# EnigmaMon.net
KiCad netlist of a schematic drawn in EAGLE
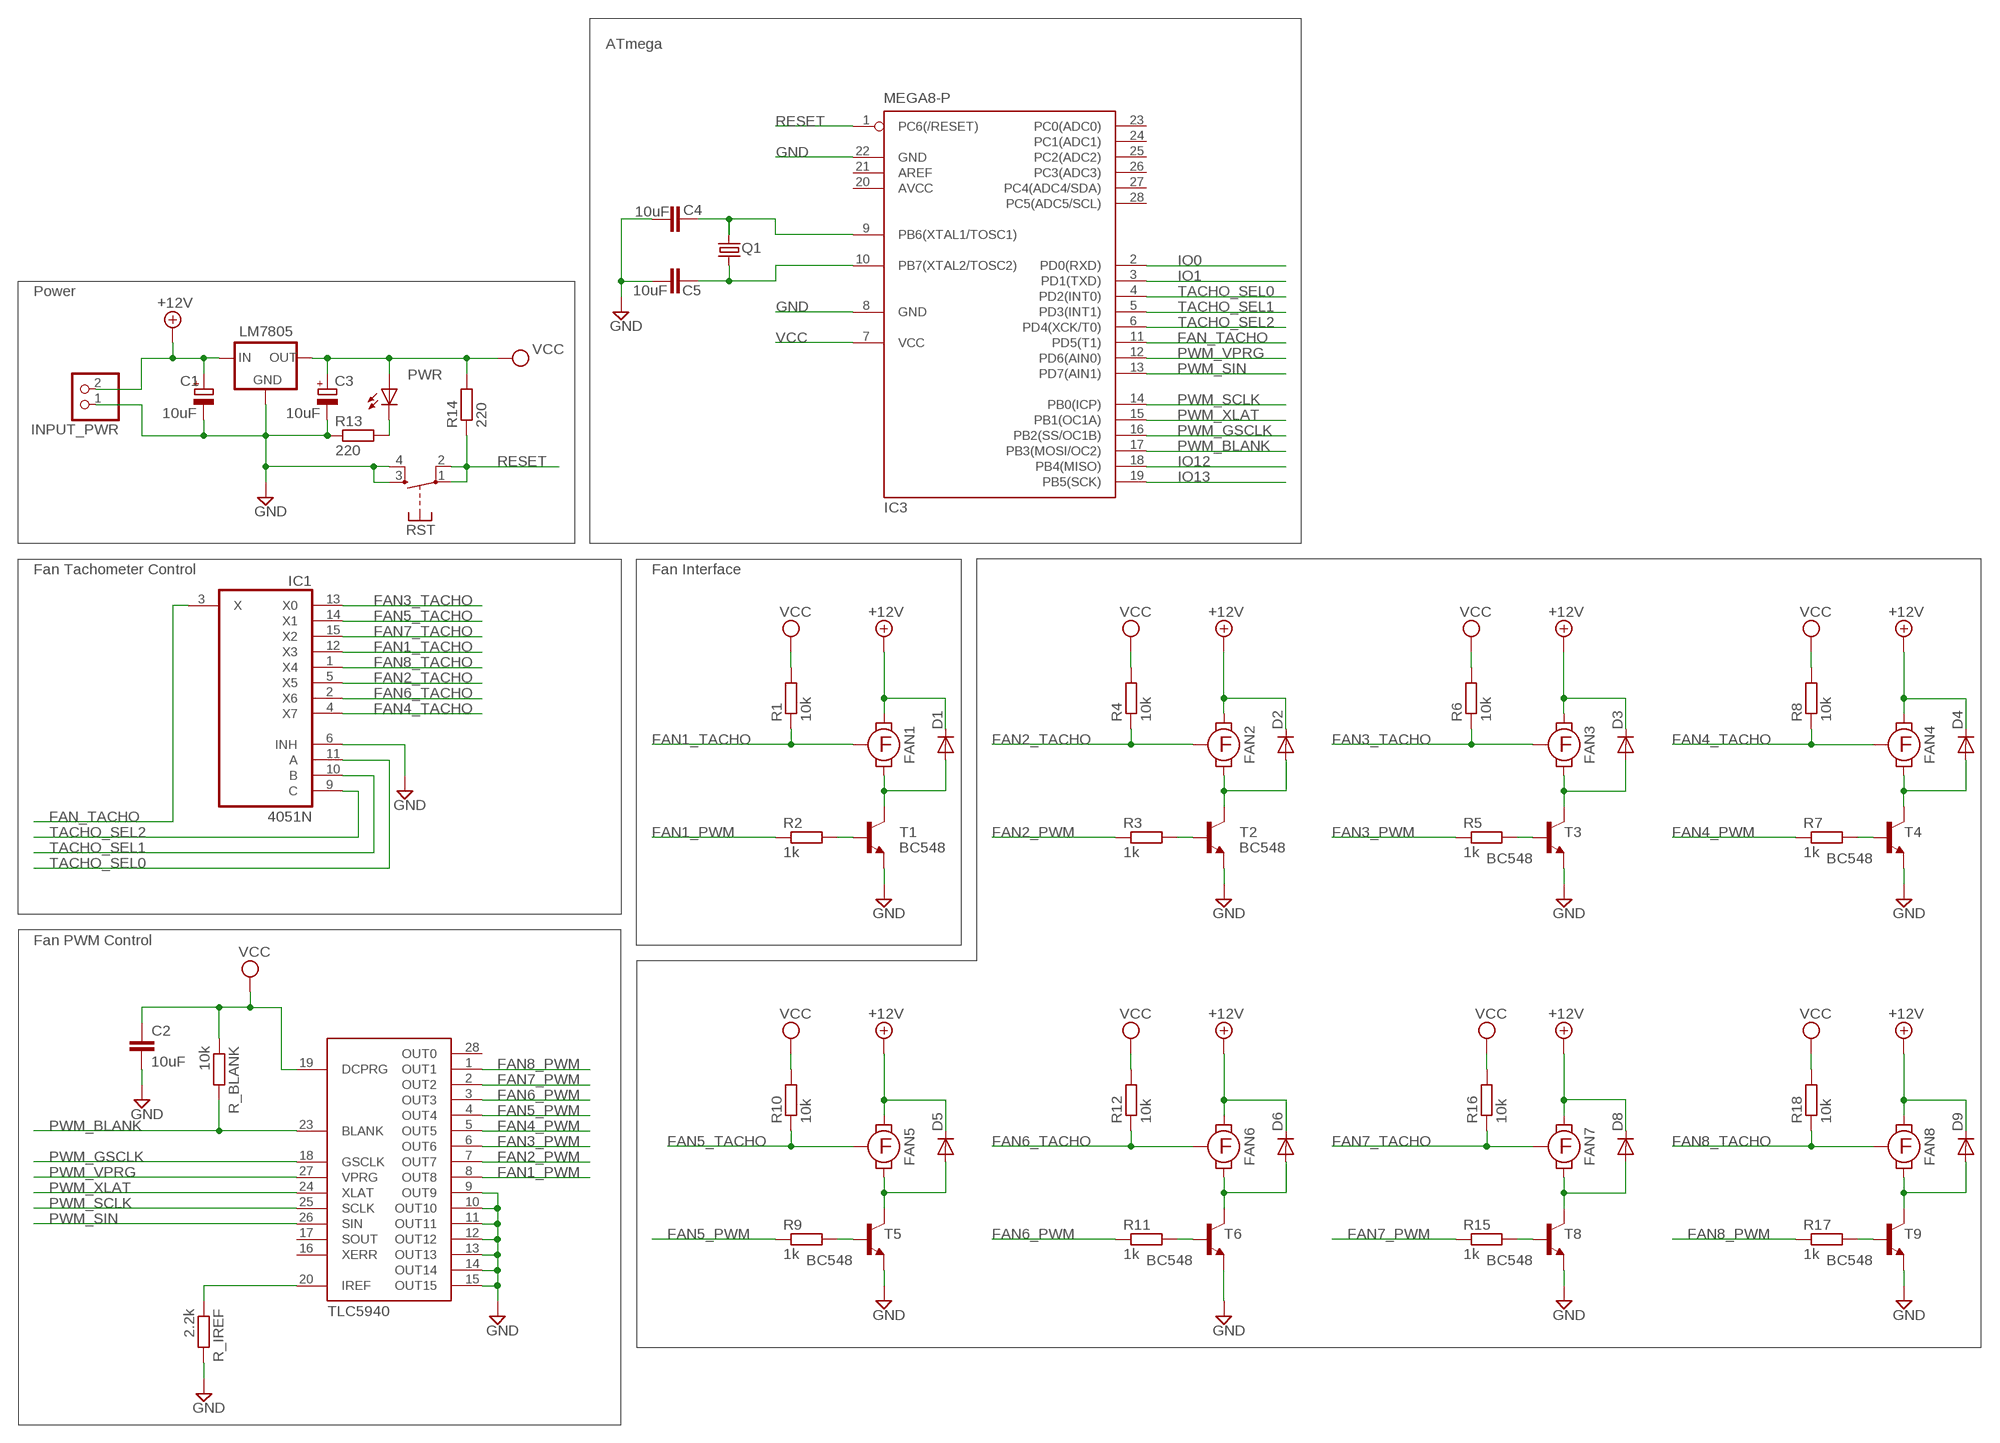
[diagram p0: schematic, sheet 1]

(export (version "E")
  (design (tool "Eeschema 10.0.6"))
  (components
    (comp (ref "C1")
      (value "10uF")
      (footprint "eagle-import:E2,5-6")
      (libsource (lib "eagle-import") (part "CPOL-EUE2.5-6"))
    )
    (comp (ref "C2")
      (value "10uF")
      (footprint "eagle-import:C025-025X050")
      (libsource (lib "eagle-import") (part "C-EU025-025X050"))
    )
    (comp (ref "C3")
      (value "10uF")
      (footprint "eagle-import:E2,5-6")
      (libsource (lib "eagle-import") (part "CPOL-EUE2.5-6"))
    )
    (comp (ref "C4")
      (value "10uF")
      (footprint "eagle-import:C025-025X050")
      (libsource (lib "eagle-import") (part "C-EU025-025X050"))
    )
    (comp (ref "C5")
      (value "10uF")
      (footprint "eagle-import:C025-025X050")
      (libsource (lib "eagle-import") (part "C-EU025-025X050"))
    )
    (comp (ref "D1")
      (value "DIODE-D-5")
      (footprint "eagle-import:D-5")
      (libsource (lib "eagle-import") (part "DIODE-D-5"))
    )
    (comp (ref "D2")
      (value "DIODE-D-5")
      (footprint "eagle-import:D-5")
      (libsource (lib "eagle-import") (part "DIODE-D-5"))
    )
    (comp (ref "D3")
      (value "DIODE-D-5")
      (footprint "eagle-import:D-5")
      (libsource (lib "eagle-import") (part "DIODE-D-5"))
    )
    (comp (ref "D4")
      (value "DIODE-D-5")
      (footprint "eagle-import:D-5")
      (libsource (lib "eagle-import") (part "DIODE-D-5"))
    )
    (comp (ref "D5")
      (value "DIODE-D-5")
      (footprint "eagle-import:D-5")
      (libsource (lib "eagle-import") (part "DIODE-D-5"))
    )
    (comp (ref "D6")
      (value "DIODE-D-5")
      (footprint "eagle-import:D-5")
      (libsource (lib "eagle-import") (part "DIODE-D-5"))
    )
    (comp (ref "D8")
      (value "DIODE-D-5")
      (footprint "eagle-import:D-5")
      (libsource (lib "eagle-import") (part "DIODE-D-5"))
    )
    (comp (ref "D9")
      (value "DIODE-D-5")
      (footprint "eagle-import:D-5")
      (libsource (lib "eagle-import") (part "DIODE-D-5"))
    )
    (comp (ref "FAN1")
      (value "FAN")
      (footprint "eagle-import:FAN_HEADER")
      (libsource (lib "eagle-import") (part "FAN"))
    )
    (comp (ref "FAN2")
      (value "FAN")
      (footprint "eagle-import:FAN_HEADER")
      (libsource (lib "eagle-import") (part "FAN"))
    )
    (comp (ref "FAN3")
      (value "FAN")
      (footprint "eagle-import:FAN_HEADER")
      (libsource (lib "eagle-import") (part "FAN"))
    )
    (comp (ref "FAN4")
      (value "FAN")
      (footprint "eagle-import:FAN_HEADER")
      (libsource (lib "eagle-import") (part "FAN"))
    )
    (comp (ref "FAN5")
      (value "FAN")
      (footprint "eagle-import:FAN_HEADER")
      (libsource (lib "eagle-import") (part "FAN"))
    )
    (comp (ref "FAN6")
      (value "FAN")
      (footprint "eagle-import:FAN_HEADER")
      (libsource (lib "eagle-import") (part "FAN"))
    )
    (comp (ref "FAN7")
      (value "FAN")
      (footprint "eagle-import:FAN_HEADER")
      (libsource (lib "eagle-import") (part "FAN"))
    )
    (comp (ref "FAN8")
      (value "FAN")
      (footprint "eagle-import:FAN_HEADER")
      (libsource (lib "eagle-import") (part "FAN"))
    )
    (comp (ref "IC1")
      (value "4051N")
      (footprint "eagle-import:DIL16")
      (libsource (lib "eagle-import") (part "4051N"))
    )
    (comp (ref "IC2")
      (value "TLC5940")
      (footprint "eagle-import:DIL28-3")
      (libsource (lib "eagle-import") (part "TLC5940"))
    )
    (comp (ref "IC3")
      (value "MEGA8-P")
      (footprint "eagle-import:DIL28-3")
      (libsource (lib "eagle-import") (part "MEGA8-P"))
    )
    (comp (ref "INPUT_PWR")
      (value "PINHD-1X2")
      (footprint "eagle-import:1X02")
      (libsource (lib "eagle-import") (part "PINHD-1X2"))
    )
    (comp (ref "LM7805")
      (value "78XXL")
      (footprint "eagle-import:78XXL")
      (libsource (lib "eagle-import") (part "78XXL"))
    )
    (comp (ref "PWR")
      (value "LED3MM")
      (footprint "eagle-import:LED3MM")
      (libsource (lib "eagle-import") (part "LED3MM"))
    )
    (comp (ref "Q1")
      (value "CRYSTALHC49S")
      (footprint "eagle-import:HC49_S")
      (libsource (lib "eagle-import") (part "CRYSTALHC49S"))
    )
    (comp (ref "R1")
      (value "10k")
      (footprint "eagle-import:0204_5")
      (libsource (lib "eagle-import") (part "R-EU_0204/5"))
    )
    (comp (ref "R2")
      (value "1k")
      (footprint "eagle-import:0204_5")
      (libsource (lib "eagle-import") (part "R-EU_0204/5"))
    )
    (comp (ref "R3")
      (value "1k")
      (footprint "eagle-import:0204_5")
      (libsource (lib "eagle-import") (part "R-EU_0204/5"))
    )
    (comp (ref "R4")
      (value "10k")
      (footprint "eagle-import:0204_5")
      (libsource (lib "eagle-import") (part "R-EU_0204/5"))
    )
    (comp (ref "R5")
      (value "1k")
      (footprint "eagle-import:0204_5")
      (libsource (lib "eagle-import") (part "R-EU_0204/5"))
    )
    (comp (ref "R6")
      (value "10k")
      (footprint "eagle-import:0204_5")
      (libsource (lib "eagle-import") (part "R-EU_0204/5"))
    )
    (comp (ref "R7")
      (value "1k")
      (footprint "eagle-import:0204_5")
      (libsource (lib "eagle-import") (part "R-EU_0204/5"))
    )
    (comp (ref "R8")
      (value "10k")
      (footprint "eagle-import:0204_5")
      (libsource (lib "eagle-import") (part "R-EU_0204/5"))
    )
    (comp (ref "R9")
      (value "1k")
      (footprint "eagle-import:0204_5")
      (libsource (lib "eagle-import") (part "R-EU_0204/5"))
    )
    (comp (ref "R10")
      (value "10k")
      (footprint "eagle-import:0204_5")
      (libsource (lib "eagle-import") (part "R-EU_0204/5"))
    )
    (comp (ref "R11")
      (value "1k")
      (footprint "eagle-import:0204_5")
      (libsource (lib "eagle-import") (part "R-EU_0204/5"))
    )
    (comp (ref "R12")
      (value "10k")
      (footprint "eagle-import:0204_5")
      (libsource (lib "eagle-import") (part "R-EU_0204/5"))
    )
    (comp (ref "R13")
      (value "220")
      (footprint "eagle-import:0204_7")
      (libsource (lib "eagle-import") (part "R-EU_0204/7"))
    )
    (comp (ref "R14")
      (value "220")
      (footprint "eagle-import:0204_7")
      (libsource (lib "eagle-import") (part "R-EU_0204/7"))
    )
    (comp (ref "R15")
      (value "1k")
      (footprint "eagle-import:0204_5")
      (libsource (lib "eagle-import") (part "R-EU_0204/5"))
    )
    (comp (ref "R16")
      (value "10k")
      (footprint "eagle-import:0204_5")
      (libsource (lib "eagle-import") (part "R-EU_0204/5"))
    )
    (comp (ref "R17")
      (value "1k")
      (footprint "eagle-import:0204_5")
      (libsource (lib "eagle-import") (part "R-EU_0204/5"))
    )
    (comp (ref "R18")
      (value "10k")
      (footprint "eagle-import:0204_5")
      (libsource (lib "eagle-import") (part "R-EU_0204/5"))
    )
    (comp (ref "RST")
      (value "DTS6")
      (footprint "eagle-import:DTS6")
      (libsource (lib "eagle-import") (part "DTS6"))
    )
    (comp (ref "R_BLANK")
      (value "10k")
      (footprint "eagle-import:0204_7")
      (libsource (lib "eagle-import") (part "R-EU_0204/7"))
    )
    (comp (ref "R_IREF")
      (value "2.2k")
      (footprint "eagle-import:0204_7")
      (libsource (lib "eagle-import") (part "R-EU_0204/7"))
    )
    (comp (ref "T1")
      (value "BC548")
      (footprint "eagle-import:TO92")
      (libsource (lib "eagle-import") (part "BC547"))
    )
    (comp (ref "T2")
      (value "BC548")
      (footprint "eagle-import:TO92")
      (libsource (lib "eagle-import") (part "BC547"))
    )
    (comp (ref "T3")
      (value "BC548")
      (footprint "eagle-import:TO92")
      (libsource (lib "eagle-import") (part "BC547"))
    )
    (comp (ref "T4")
      (value "BC548")
      (footprint "eagle-import:TO92")
      (libsource (lib "eagle-import") (part "BC547"))
    )
    (comp (ref "T5")
      (value "BC548")
      (footprint "eagle-import:TO92")
      (libsource (lib "eagle-import") (part "BC547"))
    )
    (comp (ref "T6")
      (value "BC548")
      (footprint "eagle-import:TO92")
      (libsource (lib "eagle-import") (part "BC547"))
    )
    (comp (ref "T8")
      (value "BC548")
      (footprint "eagle-import:TO92")
      (libsource (lib "eagle-import") (part "BC547"))
    )
    (comp (ref "T9")
      (value "BC548")
      (footprint "eagle-import:TO92")
      (libsource (lib "eagle-import") (part "BC547"))
    )
  )
  (nets
    (net (code "1") (name "+12V") (class "Default")
      (node (ref "C1") (pin "+") (pinfunction "+_+") (pintype "passive"))
      (node (ref "D1") (pin "C") (pinfunction "C_C") (pintype "passive"))
      (node (ref "D2") (pin "C") (pinfunction "C_C") (pintype "passive"))
      (node (ref "D3") (pin "C") (pinfunction "C_C") (pintype "passive"))
      (node (ref "D4") (pin "C") (pinfunction "C_C") (pintype "passive"))
      (node (ref "D5") (pin "C") (pinfunction "C_C") (pintype "passive"))
      (node (ref "D6") (pin "C") (pinfunction "C_C") (pintype "passive"))
      (node (ref "D8") (pin "C") (pinfunction "C_C") (pintype "passive"))
      (node (ref "D9") (pin "C") (pinfunction "C_C") (pintype "passive"))
      (node (ref "FAN1") (pin "VCC") (pinfunction "VCC_VCC") (pintype "power_in"))
      (node (ref "FAN2") (pin "VCC") (pinfunction "VCC_VCC") (pintype "power_in"))
      (node (ref "FAN3") (pin "VCC") (pinfunction "VCC_VCC") (pintype "power_in"))
      (node (ref "FAN4") (pin "VCC") (pinfunction "VCC_VCC") (pintype "power_in"))
      (node (ref "FAN5") (pin "VCC") (pinfunction "VCC_VCC") (pintype "power_in"))
      (node (ref "FAN6") (pin "VCC") (pinfunction "VCC_VCC") (pintype "power_in"))
      (node (ref "FAN7") (pin "VCC") (pinfunction "VCC_VCC") (pintype "power_in"))
      (node (ref "FAN8") (pin "VCC") (pinfunction "VCC_VCC") (pintype "power_in"))
      (node (ref "INPUT_PWR") (pin "2") (pinfunction "2_2") (pintype "passive"))
      (node (ref "LM7805") (pin "IN") (pinfunction "IN_IN") (pintype "input"))
    )
    (net (code "2") (name "/AVCC") (class "Default")
      (node (ref "IC3") (pin "20") (pinfunction "AVCC_20") (pintype "power_in"))
    )
    (net (code "3") (name "/FAN1_PWM") (class "Default")
      (node (ref "IC2") (pin "8") (pinfunction "OUT8_8") (pintype "output"))
      (node (ref "R2") (pin "1") (pinfunction "1_1") (pintype "passive"))
    )
    (net (code "4") (name "/FAN1_TACHO") (class "Default")
      (node (ref "FAN1") (pin "TACHO") (pinfunction "TACHO_TACHO") (pintype "output"))
      (node (ref "IC1") (pin "12") (pinfunction "X3_12") (pintype "bidirectional"))
      (node (ref "R1") (pin "1") (pinfunction "1_1") (pintype "passive"))
    )
    (net (code "5") (name "/FAN2_PWM") (class "Default")
      (node (ref "IC2") (pin "7") (pinfunction "OUT7_7") (pintype "output"))
      (node (ref "R3") (pin "1") (pinfunction "1_1") (pintype "passive"))
    )
    (net (code "6") (name "/FAN2_TACHO") (class "Default")
      (node (ref "FAN2") (pin "TACHO") (pinfunction "TACHO_TACHO") (pintype "output"))
      (node (ref "IC1") (pin "5") (pinfunction "X5_5") (pintype "bidirectional"))
      (node (ref "R4") (pin "1") (pinfunction "1_1") (pintype "passive"))
    )
    (net (code "7") (name "/FAN3_PWM") (class "Default")
      (node (ref "IC2") (pin "6") (pinfunction "OUT6_6") (pintype "output"))
      (node (ref "R5") (pin "1") (pinfunction "1_1") (pintype "passive"))
    )
    (net (code "8") (name "/FAN3_TACHO") (class "Default")
      (node (ref "FAN3") (pin "TACHO") (pinfunction "TACHO_TACHO") (pintype "output"))
      (node (ref "IC1") (pin "13") (pinfunction "X0_13") (pintype "bidirectional"))
      (node (ref "R6") (pin "1") (pinfunction "1_1") (pintype "passive"))
    )
    (net (code "9") (name "/FAN4_PWM") (class "Default")
      (node (ref "IC2") (pin "5") (pinfunction "OUT5_5") (pintype "output"))
      (node (ref "R7") (pin "1") (pinfunction "1_1") (pintype "passive"))
    )
    (net (code "10") (name "/FAN4_TACHO") (class "Default")
      (node (ref "FAN4") (pin "TACHO") (pinfunction "TACHO_TACHO") (pintype "output"))
      (node (ref "IC1") (pin "4") (pinfunction "X7_4") (pintype "bidirectional"))
      (node (ref "R8") (pin "1") (pinfunction "1_1") (pintype "passive"))
    )
    (net (code "11") (name "/FAN5_PWM") (class "Default")
      (node (ref "IC2") (pin "4") (pinfunction "OUT4_4") (pintype "output"))
      (node (ref "R9") (pin "1") (pinfunction "1_1") (pintype "passive"))
    )
    (net (code "12") (name "/FAN5_TACHO") (class "Default")
      (node (ref "FAN5") (pin "TACHO") (pinfunction "TACHO_TACHO") (pintype "output"))
      (node (ref "IC1") (pin "14") (pinfunction "X1_14") (pintype "bidirectional"))
      (node (ref "R10") (pin "1") (pinfunction "1_1") (pintype "passive"))
    )
    (net (code "13") (name "/FAN6_PWM") (class "Default")
      (node (ref "IC2") (pin "3") (pinfunction "OUT3_3") (pintype "output"))
      (node (ref "R11") (pin "1") (pinfunction "1_1") (pintype "passive"))
    )
    (net (code "14") (name "/FAN6_TACHO") (class "Default")
      (node (ref "FAN6") (pin "TACHO") (pinfunction "TACHO_TACHO") (pintype "output"))
      (node (ref "IC1") (pin "2") (pinfunction "X6_2") (pintype "bidirectional"))
      (node (ref "R12") (pin "1") (pinfunction "1_1") (pintype "passive"))
    )
    (net (code "15") (name "/FAN7_PWM") (class "Default")
      (node (ref "IC2") (pin "2") (pinfunction "OUT2_2") (pintype "output"))
      (node (ref "R15") (pin "1") (pinfunction "1_1") (pintype "passive"))
    )
    (net (code "16") (name "/FAN7_TACHO") (class "Default")
      (node (ref "FAN7") (pin "TACHO") (pinfunction "TACHO_TACHO") (pintype "output"))
      (node (ref "IC1") (pin "15") (pinfunction "X2_15") (pintype "bidirectional"))
      (node (ref "R16") (pin "1") (pinfunction "1_1") (pintype "passive"))
    )
    (net (code "17") (name "/FAN8_PWM") (class "Default")
      (node (ref "IC2") (pin "1") (pinfunction "OUT1_1") (pintype "output"))
      (node (ref "R17") (pin "1") (pinfunction "1_1") (pintype "passive"))
    )
    (net (code "18") (name "/FAN8_TACHO") (class "Default")
      (node (ref "FAN8") (pin "TACHO") (pinfunction "TACHO_TACHO") (pintype "output"))
      (node (ref "IC1") (pin "1") (pinfunction "X4_1") (pintype "bidirectional"))
      (node (ref "R18") (pin "1") (pinfunction "1_1") (pintype "passive"))
    )
    (net (code "19") (name "/FAN_TACHO") (class "Default")
      (node (ref "IC1") (pin "3") (pinfunction "X_3") (pintype "bidirectional"))
      (node (ref "IC3") (pin "11") (pinfunction "PD5(T1)_11") (pintype "bidirectional"))
    )
    (net (code "20") (name "/IO0") (class "Default")
      (node (ref "IC3") (pin "2") (pinfunction "PD0(RXD)_2") (pintype "bidirectional"))
    )
    (net (code "21") (name "/IO1") (class "Default")
      (node (ref "IC3") (pin "3") (pinfunction "PD1(TXD)_3") (pintype "bidirectional"))
    )
    (net (code "22") (name "/IO12") (class "Default")
      (node (ref "IC3") (pin "18") (pinfunction "PB4(MISO)_18") (pintype "bidirectional"))
    )
    (net (code "23") (name "/IO13") (class "Default")
      (node (ref "IC3") (pin "19") (pinfunction "PB5(SCK)_19") (pintype "bidirectional"))
    )
    (net (code "24") (name "/PWM_BLANK") (class "Default")
      (node (ref "IC2") (pin "23") (pinfunction "BLANK_23") (pintype "bidirectional"))
      (node (ref "IC3") (pin "17") (pinfunction "PB3(MOSI/OC2)_17") (pintype "bidirectional"))
      (node (ref "R_BLANK") (pin "2") (pinfunction "2_2") (pintype "passive"))
    )
    (net (code "25") (name "/PWM_GSCLK") (class "Default")
      (node (ref "IC2") (pin "18") (pinfunction "GSCLK_18") (pintype "bidirectional"))
      (node (ref "IC3") (pin "16") (pinfunction "PB2(SS/OC1B)_16") (pintype "bidirectional"))
    )
    (net (code "26") (name "/PWM_SCLK") (class "Default")
      (node (ref "IC2") (pin "25") (pinfunction "SCLK_25") (pintype "bidirectional"))
      (node (ref "IC3") (pin "14") (pinfunction "PB0(ICP)_14") (pintype "bidirectional"))
    )
    (net (code "27") (name "/PWM_SIN") (class "Default")
      (node (ref "IC2") (pin "26") (pinfunction "SIN_26") (pintype "bidirectional"))
      (node (ref "IC3") (pin "13") (pinfunction "PD7(AIN1)_13") (pintype "bidirectional"))
    )
    (net (code "28") (name "/PWM_VPRG") (class "Default")
      (node (ref "IC2") (pin "27") (pinfunction "VPRG_27") (pintype "bidirectional"))
      (node (ref "IC3") (pin "12") (pinfunction "PD6(AIN0)_12") (pintype "bidirectional"))
    )
    (net (code "29") (name "/PWM_XLAT") (class "Default")
      (node (ref "IC2") (pin "24") (pinfunction "XLAT_24") (pintype "bidirectional"))
      (node (ref "IC3") (pin "15") (pinfunction "PB1(OC1A)_15") (pintype "bidirectional"))
    )
    (net (code "30") (name "/RESET") (class "Default")
      (node (ref "IC3") (pin "1") (pinfunction "PC6(/RESET)_1") (pintype "bidirectional"))
      (node (ref "R14") (pin "1") (pinfunction "1_1") (pintype "passive"))
      (node (ref "RST") (pin "1") (pinfunction "P_1") (pintype "passive"))
      (node (ref "RST") (pin "2") (pinfunction "P_2") (pintype "passive"))
    )
    (net (code "31") (name "/TACHO_SEL0") (class "Default")
      (node (ref "IC1") (pin "11") (pinfunction "A_11") (pintype "input"))
      (node (ref "IC3") (pin "4") (pinfunction "PD2(INT0)_4") (pintype "bidirectional"))
    )
    (net (code "32") (name "/TACHO_SEL1") (class "Default")
      (node (ref "IC1") (pin "10") (pinfunction "B_10") (pintype "input"))
      (node (ref "IC3") (pin "5") (pinfunction "PD3(INT1)_5") (pintype "bidirectional"))
    )
    (net (code "33") (name "/TACHO_SEL2") (class "Default")
      (node (ref "IC1") (pin "9") (pinfunction "C_9") (pintype "input"))
      (node (ref "IC3") (pin "6") (pinfunction "PD4(XCK/T0)_6") (pintype "bidirectional"))
    )
    (net (code "34") (name "GND") (class "Default")
      (node (ref "C1") (pin "-") (pinfunction "-_-") (pintype "passive"))
      (node (ref "C2") (pin "2") (pinfunction "2_2") (pintype "passive"))
      (node (ref "C3") (pin "-") (pinfunction "-_-") (pintype "passive"))
      (node (ref "C4") (pin "1") (pinfunction "1_1") (pintype "passive"))
      (node (ref "C5") (pin "1") (pinfunction "1_1") (pintype "passive"))
      (node (ref "IC1") (pin "6") (pinfunction "INH_6") (pintype "input"))
      (node (ref "IC2") (pin "10") (pinfunction "OUT10_10") (pintype "output"))
      (node (ref "IC2") (pin "11") (pinfunction "OUT11_11") (pintype "output"))
      (node (ref "IC2") (pin "12") (pinfunction "OUT12_12") (pintype "output"))
      (node (ref "IC2") (pin "13") (pinfunction "OUT13_13") (pintype "output"))
      (node (ref "IC2") (pin "14") (pinfunction "OUT14_14") (pintype "output"))
      (node (ref "IC2") (pin "15") (pinfunction "OUT15_15") (pintype "output"))
      (node (ref "IC2") (pin "9") (pinfunction "OUT9_9") (pintype "output"))
      (node (ref "IC3") (pin "22") (pinfunction "GND_22") (pintype "power_in"))
      (node (ref "IC3") (pin "8") (pinfunction "GND_8") (pintype "power_in"))
      (node (ref "INPUT_PWR") (pin "1") (pinfunction "1_1") (pintype "passive"))
      (node (ref "LM7805") (pin "GND") (pinfunction "GND_GND") (pintype "input"))
      (node (ref "R13") (pin "1") (pinfunction "1_1") (pintype "passive"))
      (node (ref "RST") (pin "3") (pinfunction "S_3") (pintype "passive"))
      (node (ref "RST") (pin "4") (pinfunction "S_4") (pintype "passive"))
      (node (ref "R_IREF") (pin "2") (pinfunction "2_2") (pintype "passive"))
      (node (ref "T1") (pin "1") (pinfunction "E_1") (pintype "passive"))
      (node (ref "T2") (pin "1") (pinfunction "E_1") (pintype "passive"))
      (node (ref "T3") (pin "1") (pinfunction "E_1") (pintype "passive"))
      (node (ref "T4") (pin "1") (pinfunction "E_1") (pintype "passive"))
      (node (ref "T5") (pin "1") (pinfunction "E_1") (pintype "passive"))
      (node (ref "T6") (pin "1") (pinfunction "E_1") (pintype "passive"))
      (node (ref "T8") (pin "1") (pinfunction "E_1") (pintype "passive"))
      (node (ref "T9") (pin "1") (pinfunction "E_1") (pintype "passive"))
    )
    (net (code "35") (name "Net-(IC2A-IREF)") (class "Default")
      (node (ref "IC2") (pin "20") (pinfunction "IREF_20") (pintype "bidirectional"))
      (node (ref "R_IREF") (pin "1") (pinfunction "1_1") (pintype "passive"))
    )
    (net (code "36") (name "Net-(IC3-PB6(XTAL1{slash}TOSC1))") (class "Default")
      (node (ref "C4") (pin "2") (pinfunction "2_2") (pintype "passive"))
      (node (ref "IC3") (pin "9") (pinfunction "PB6(XTAL1/TOSC1)_9") (pintype "bidirectional"))
      (node (ref "Q1") (pin "2") (pinfunction "2_2") (pintype "passive"))
    )
    (net (code "37") (name "Net-(IC3-PB7(XTAL2{slash}TOSC2))") (class "Default")
      (node (ref "C5") (pin "2") (pinfunction "2_2") (pintype "passive"))
      (node (ref "IC3") (pin "10") (pinfunction "PB7(XTAL2/TOSC2)_10") (pintype "bidirectional"))
      (node (ref "Q1") (pin "1") (pinfunction "1_1") (pintype "passive"))
    )
    (net (code "38") (name "Net-(PWR-C)") (class "Default")
      (node (ref "PWR") (pin "K") (pinfunction "C_K") (pintype "passive"))
      (node (ref "R13") (pin "2") (pinfunction "2_2") (pintype "passive"))
    )
    (net (code "39") (name "Net-(T1-B)") (class "Default")
      (node (ref "R2") (pin "2") (pinfunction "2_2") (pintype "passive"))
      (node (ref "T1") (pin "2") (pinfunction "B_2") (pintype "passive"))
    )
    (net (code "40") (name "Net-(T1-C)") (class "Default")
      (node (ref "D1") (pin "A") (pinfunction "A_A") (pintype "passive"))
      (node (ref "FAN1") (pin "GND") (pinfunction "GND_GND") (pintype "power_in"))
      (node (ref "T1") (pin "3") (pinfunction "C_3") (pintype "passive"))
    )
    (net (code "41") (name "Net-(T2-B)") (class "Default")
      (node (ref "R3") (pin "2") (pinfunction "2_2") (pintype "passive"))
      (node (ref "T2") (pin "2") (pinfunction "B_2") (pintype "passive"))
    )
    (net (code "42") (name "Net-(T2-C)") (class "Default")
      (node (ref "D2") (pin "A") (pinfunction "A_A") (pintype "passive"))
      (node (ref "FAN2") (pin "GND") (pinfunction "GND_GND") (pintype "power_in"))
      (node (ref "T2") (pin "3") (pinfunction "C_3") (pintype "passive"))
    )
    (net (code "43") (name "Net-(T3-B)") (class "Default")
      (node (ref "R5") (pin "2") (pinfunction "2_2") (pintype "passive"))
      (node (ref "T3") (pin "2") (pinfunction "B_2") (pintype "passive"))
    )
    (net (code "44") (name "Net-(T3-C)") (class "Default")
      (node (ref "D3") (pin "A") (pinfunction "A_A") (pintype "passive"))
      (node (ref "FAN3") (pin "GND") (pinfunction "GND_GND") (pintype "power_in"))
      (node (ref "T3") (pin "3") (pinfunction "C_3") (pintype "passive"))
    )
    (net (code "45") (name "Net-(T4-B)") (class "Default")
      (node (ref "R7") (pin "2") (pinfunction "2_2") (pintype "passive"))
      (node (ref "T4") (pin "2") (pinfunction "B_2") (pintype "passive"))
    )
    (net (code "46") (name "Net-(T4-C)") (class "Default")
      (node (ref "D4") (pin "A") (pinfunction "A_A") (pintype "passive"))
      (node (ref "FAN4") (pin "GND") (pinfunction "GND_GND") (pintype "power_in"))
      (node (ref "T4") (pin "3") (pinfunction "C_3") (pintype "passive"))
    )
    (net (code "47") (name "Net-(T5-B)") (class "Default")
      (node (ref "R9") (pin "2") (pinfunction "2_2") (pintype "passive"))
      (node (ref "T5") (pin "2") (pinfunction "B_2") (pintype "passive"))
    )
    (net (code "48") (name "Net-(T5-C)") (class "Default")
      (node (ref "D5") (pin "A") (pinfunction "A_A") (pintype "passive"))
      (node (ref "FAN5") (pin "GND") (pinfunction "GND_GND") (pintype "power_in"))
      (node (ref "T5") (pin "3") (pinfunction "C_3") (pintype "passive"))
    )
    (net (code "49") (name "Net-(T6-B)") (class "Default")
      (node (ref "R11") (pin "2") (pinfunction "2_2") (pintype "passive"))
      (node (ref "T6") (pin "2") (pinfunction "B_2") (pintype "passive"))
    )
    (net (code "50") (name "Net-(T6-C)") (class "Default")
      (node (ref "D6") (pin "A") (pinfunction "A_A") (pintype "passive"))
      (node (ref "FAN6") (pin "GND") (pinfunction "GND_GND") (pintype "power_in"))
      (node (ref "T6") (pin "3") (pinfunction "C_3") (pintype "passive"))
    )
    (net (code "51") (name "Net-(T8-B)") (class "Default")
      (node (ref "R15") (pin "2") (pinfunction "2_2") (pintype "passive"))
      (node (ref "T8") (pin "2") (pinfunction "B_2") (pintype "passive"))
    )
    (net (code "52") (name "Net-(T8-C)") (class "Default")
      (node (ref "D8") (pin "A") (pinfunction "A_A") (pintype "passive"))
      (node (ref "FAN7") (pin "GND") (pinfunction "GND_GND") (pintype "power_in"))
      (node (ref "T8") (pin "3") (pinfunction "C_3") (pintype "passive"))
    )
    (net (code "53") (name "Net-(T9-B)") (class "Default")
      (node (ref "R17") (pin "2") (pinfunction "2_2") (pintype "passive"))
      (node (ref "T9") (pin "2") (pinfunction "B_2") (pintype "passive"))
    )
    (net (code "54") (name "Net-(T9-C)") (class "Default")
      (node (ref "D9") (pin "A") (pinfunction "A_A") (pintype "passive"))
      (node (ref "FAN8") (pin "GND") (pinfunction "GND_GND") (pintype "power_in"))
      (node (ref "T9") (pin "3") (pinfunction "C_3") (pintype "passive"))
    )
    (net (code "55") (name "VCC") (class "Default")
      (node (ref "C2") (pin "1") (pinfunction "1_1") (pintype "passive"))
      (node (ref "C3") (pin "+") (pinfunction "+_+") (pintype "passive"))
      (node (ref "IC2") (pin "19") (pinfunction "DCPRG_19") (pintype "bidirectional"))
      (node (ref "IC3") (pin "7") (pinfunction "VCC_7") (pintype "power_in"))
      (node (ref "LM7805") (pin "OUT") (pinfunction "OUT_OUT") (pintype "passive"))
      (node (ref "PWR") (pin "A") (pinfunction "A_A") (pintype "passive"))
      (node (ref "R1") (pin "2") (pinfunction "2_2") (pintype "passive"))
      (node (ref "R10") (pin "2") (pinfunction "2_2") (pintype "passive"))
      (node (ref "R12") (pin "2") (pinfunction "2_2") (pintype "passive"))
      (node (ref "R14") (pin "2") (pinfunction "2_2") (pintype "passive"))
      (node (ref "R16") (pin "2") (pinfunction "2_2") (pintype "passive"))
      (node (ref "R18") (pin "2") (pinfunction "2_2") (pintype "passive"))
      (node (ref "R4") (pin "2") (pinfunction "2_2") (pintype "passive"))
      (node (ref "R6") (pin "2") (pinfunction "2_2") (pintype "passive"))
      (node (ref "R8") (pin "2") (pinfunction "2_2") (pintype "passive"))
      (node (ref "R_BLANK") (pin "1") (pinfunction "1_1") (pintype "passive"))
    )
    (net (code "56") (name "unconnected-(IC2A-OUT0-Pad28)") (class "Default")
      (node (ref "IC2") (pin "28") (pinfunction "OUT0_28") (pintype "output"))
    )
    (net (code "57") (name "unconnected-(IC2A-SOUT-Pad17)") (class "Default")
      (node (ref "IC2") (pin "17") (pinfunction "SOUT_17") (pintype "bidirectional"))
    )
    (net (code "58") (name "unconnected-(IC2A-XERR-Pad16)") (class "Default")
      (node (ref "IC2") (pin "16") (pinfunction "XERR_16") (pintype "bidirectional"))
    )
    (net (code "59") (name "unconnected-(IC3-AREF-Pad21)") (class "Default")
      (node (ref "IC3") (pin "21") (pinfunction "AREF_21") (pintype "passive"))
    )
    (net (code "60") (name "unconnected-(IC3-PC0(ADC0)-Pad23)") (class "Default")
      (node (ref "IC3") (pin "23") (pinfunction "PC0(ADC0)_23") (pintype "bidirectional"))
    )
    (net (code "61") (name "unconnected-(IC3-PC1(ADC1)-Pad24)") (class "Default")
      (node (ref "IC3") (pin "24") (pinfunction "PC1(ADC1)_24") (pintype "bidirectional"))
    )
    (net (code "62") (name "unconnected-(IC3-PC2(ADC2)-Pad25)") (class "Default")
      (node (ref "IC3") (pin "25") (pinfunction "PC2(ADC2)_25") (pintype "bidirectional"))
    )
    (net (code "63") (name "unconnected-(IC3-PC3(ADC3)-Pad26)") (class "Default")
      (node (ref "IC3") (pin "26") (pinfunction "PC3(ADC3)_26") (pintype "bidirectional"))
    )
    (net (code "64") (name "unconnected-(IC3-PC4(ADC4{slash}SDA)-Pad27)") (class "Default")
      (node (ref "IC3") (pin "27") (pinfunction "PC4(ADC4/SDA)_27") (pintype "bidirectional"))
    )
    (net (code "65") (name "unconnected-(IC3-PC5(ADC5{slash}SCL)-Pad28)") (class "Default")
      (node (ref "IC3") (pin "28") (pinfunction "PC5(ADC5/SCL)_28") (pintype "bidirectional"))
    )
  )
)
